# Sheet1.net
KiCad netlist of a schematic drawn in Altium Designer
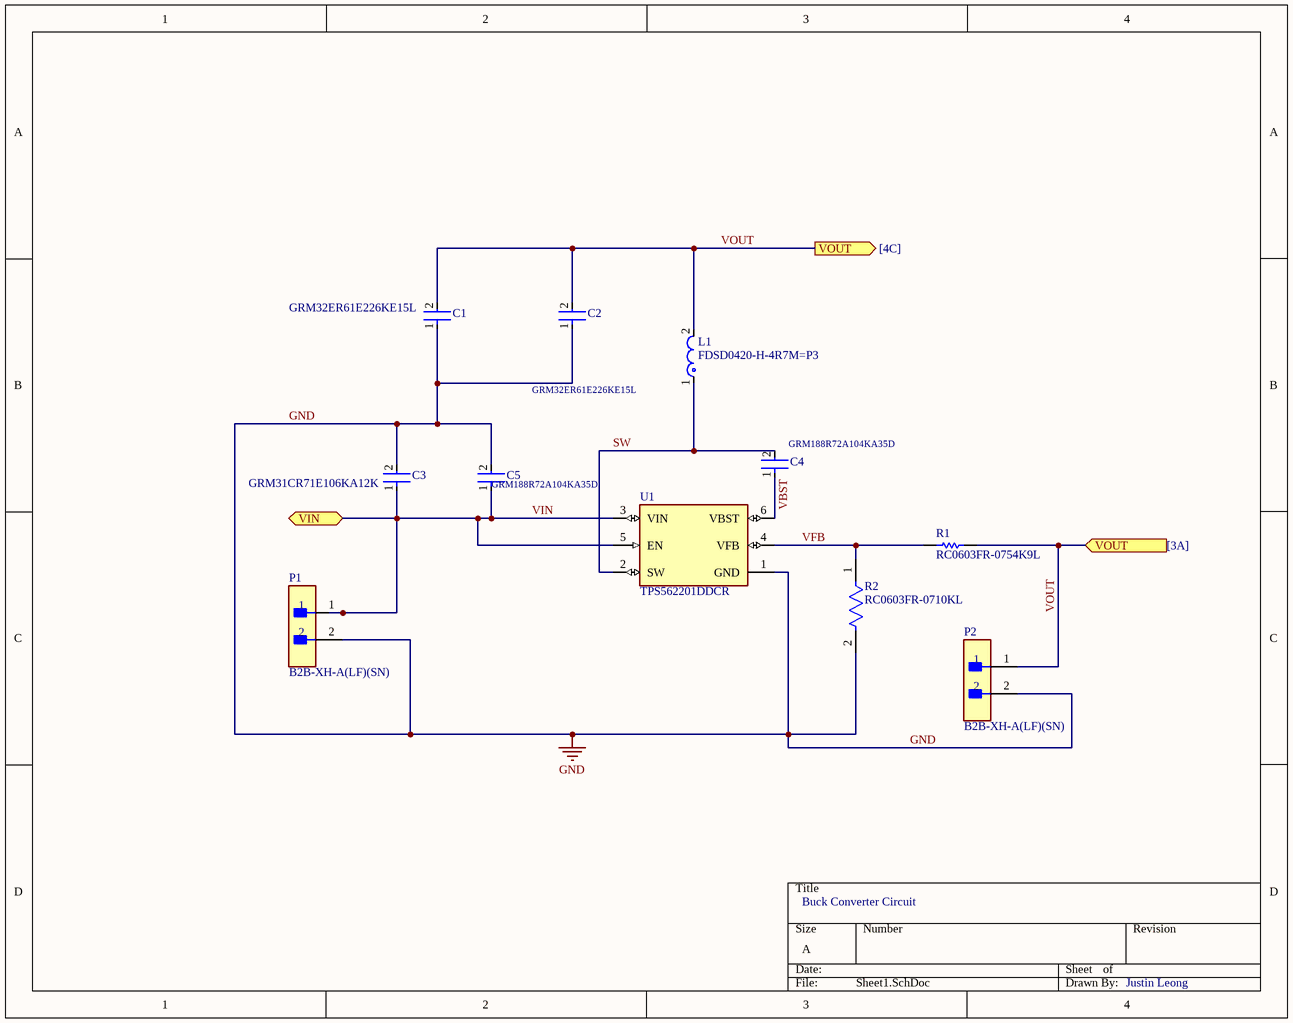
[diagram p0: Sheet1.SchDoc]

(export (version "E")
  (design (tool "Eeschema 10.0.6"))
  (components
    (comp (ref "C1")
      (value "GRM32ER61E226KE15L")
      (footprint "FP-GRM32-MFG")
      (description "CAP CER 22UF 25V X5R 1210")
      (fields
        (field (name "TOLERANCE") "10%")
        (field (name "MANUFACTURER") "Murata Electronics North America")
      )
      (libsource (lib "Altium Content Vault") (part "11868f565c42a9108669ba33697ecf6"))
    )
    (comp (ref "C2")
      (value "GRM32ER61E226KE15L")
      (footprint "FP-GRM32-MFG")
      (description "CAP CER 22UF 25V X5R 1210")
      (fields
        (field (name "TOLERANCE") "10%")
        (field (name "MANUFACTURER") "Murata Electronics North America")
      )
      (libsource (lib "Altium Content Vault") (part "11868f565c42a9108669ba33697ecf6"))
    )
    (comp (ref "C3")
      (value "GRM31CR71E106KA12K")
      (footprint "FP-GRM31C-0_2-e0_3_0_8-MFG")
      (description "Chip Multilayer Ceramic Capacitors for General Purpose, 1206, 10uF, X7R, 15%, 10%, 25V")
      (fields (field (name "TOLERANCE") "10%") (field (name "VOLTAGE") "25V"))
      (libsource (lib "Altium Content Vault") (part "02cd4be3c70576c341d710602a673aa"))
    )
    (comp (ref "C4")
      (value "GRM188R72A104KA35D")
      (footprint "FP-GRM188-0_1-e0_2_0_5-IPC_B")
      (description "Chip Multilayer Ceramic Capacitors for General Purpose, 0603, 0.10uF, X7R, 15%, 10%, 100V")
      (fields (field (name "VOLTAGE") "100V") (field (name "TOLERANCE") "10%"))
      (libsource (lib "Altium Content Vault") (part "11868f565c42a9108669ba33697ecf6"))
    )
    (comp (ref "C5")
      (value "GRM188R72A104KA35D")
      (footprint "FP-GRM188-0_1-e0_2_0_5-IPC_B")
      (description "Chip Multilayer Ceramic Capacitors for General Purpose, 0603, 0.10uF, X7R, 15%, 10%, 100V")
      (fields (field (name "VOLTAGE") "100V") (field (name "TOLERANCE") "10%"))
      (libsource (lib "Altium Content Vault") (part "11868f565c42a9108669ba33697ecf6"))
    )
    (comp (ref "L1")
      (value "FDSD0420-H-4R7M=P3")
      (footprint "FP-FDSD0420-MFG")
      (description "FIXED IND 4.7UH 2.7A 83 MOHM SMD")
      (fields (field (name "TOLERANCE") "20%"))
      (libsource (lib "Altium Content Vault") (part "4cc4b267dca4c8e51f7102f422741d8"))
    )
    (comp (ref "P1")
      (value "B2B-XH-A(LF)(SN)")
      (footprint "FP-B2B-XH-A_LF_SN-MFG")
      (description "CONN HEADER VERT 2POS 2.5MM")
      (libsource (lib "Altium Content Vault") (part "3bc925449376181038e59eaffc5286c"))
    )
    (comp (ref "P2")
      (value "B2B-XH-A(LF)(SN)")
      (footprint "FP-B2B-XH-A_LF_SN-MFG")
      (description "CONN HEADER VERT 2POS 2.5MM")
      (libsource (lib "Altium Content Vault") (part "3bc925449376181038e59eaffc5286c"))
    )
    (comp (ref "R1")
      (value "RC0603FR-0754K9L")
      (footprint "RESC1608X55X25NL10T15")
      (fields (field (name "MANUFACTURER") "Yageo"))
      (libsource (lib "Altium Content Vault") (part "RES"))
    )
    (comp (ref "R2")
      (value "RC0603FR-0710KL")
      (footprint "FP-RC0603-0_55-IPC_C")
      (description "RES 10K OHM 1% 1/10W 0603")
      (fields (field (name "TOLERANCE") "1%"))
      (libsource (lib "Altium Content Vault") (part "1029c3af85768c4190bb7ad29bc67b5"))
    )
    (comp (ref "U1")
      (value "TPS562201DDCR")
      (footprint "FP-DDC0006A-IPC_C")
      (description "Buck Yes 580KHz Adjustable 1 7V 768mV 17V 4.5V SOT-23-THIN SMD mount 1.1mm(height)")
      (libsource (lib "Justin") (part "957e164956730ea4bf6293280af19fc"))
    )
  )
  (nets
    (net (code "1") (name "/SW") (class "Default")
      (node (ref "C4") (pin "2") (pinfunction "2_2") (pintype "passive"))
      (node (ref "L1") (pin "1") (pinfunction "1_1") (pintype "passive"))
      (node (ref "U1") (pin "2") (pinfunction "SW_2") (pintype "bidirectional"))
    )
    (net (code "2") (name "/VBST") (class "Default")
      (node (ref "C4") (pin "1") (pinfunction "1_1") (pintype "passive"))
      (node (ref "U1") (pin "6") (pinfunction "VBST_6") (pintype "bidirectional"))
    )
    (net (code "3") (name "/VFB") (class "Default")
      (node (ref "R1") (pin "1") (pinfunction "1_1") (pintype "passive"))
      (node (ref "R2") (pin "1") (pinfunction "1_1") (pintype "passive"))
      (node (ref "U1") (pin "4") (pinfunction "VFB_4") (pintype "bidirectional"))
    )
    (net (code "4") (name "/VIN") (class "Default")
      (node (ref "C3") (pin "1") (pinfunction "1_1") (pintype "passive"))
      (node (ref "C5") (pin "1") (pinfunction "1_1") (pintype "passive"))
      (node (ref "P1") (pin "1") (pinfunction "1_1") (pintype "passive"))
      (node (ref "U1") (pin "3") (pinfunction "VIN_3") (pintype "bidirectional"))
      (node (ref "U1") (pin "5") (pinfunction "EN_5") (pintype "input"))
    )
    (net (code "5") (name "/VOUT") (class "Default")
      (node (ref "C1") (pin "2") (pinfunction "2_2") (pintype "passive"))
      (node (ref "C2") (pin "2") (pinfunction "2_2") (pintype "passive"))
      (node (ref "L1") (pin "2") (pinfunction "2_2") (pintype "passive"))
      (node (ref "P2") (pin "1") (pinfunction "1_1") (pintype "passive"))
      (node (ref "R1") (pin "2") (pinfunction "2_2") (pintype "passive"))
    )
    (net (code "6") (name "GND") (class "Default")
      (node (ref "C1") (pin "1") (pinfunction "1_1") (pintype "passive"))
      (node (ref "C2") (pin "1") (pinfunction "1_1") (pintype "passive"))
      (node (ref "C3") (pin "2") (pinfunction "2_2") (pintype "passive"))
      (node (ref "C5") (pin "2") (pinfunction "2_2") (pintype "passive"))
      (node (ref "P1") (pin "2") (pinfunction "2_2") (pintype "passive"))
      (node (ref "P2") (pin "2") (pinfunction "2_2") (pintype "passive"))
      (node (ref "R2") (pin "2") (pinfunction "2_2") (pintype "passive"))
      (node (ref "U1") (pin "1") (pinfunction "GND_1") (pintype "power_in"))
    )
  )
)
